# Pi1541_HAT.net
KiCad netlist of a schematic drawn in EAGLE
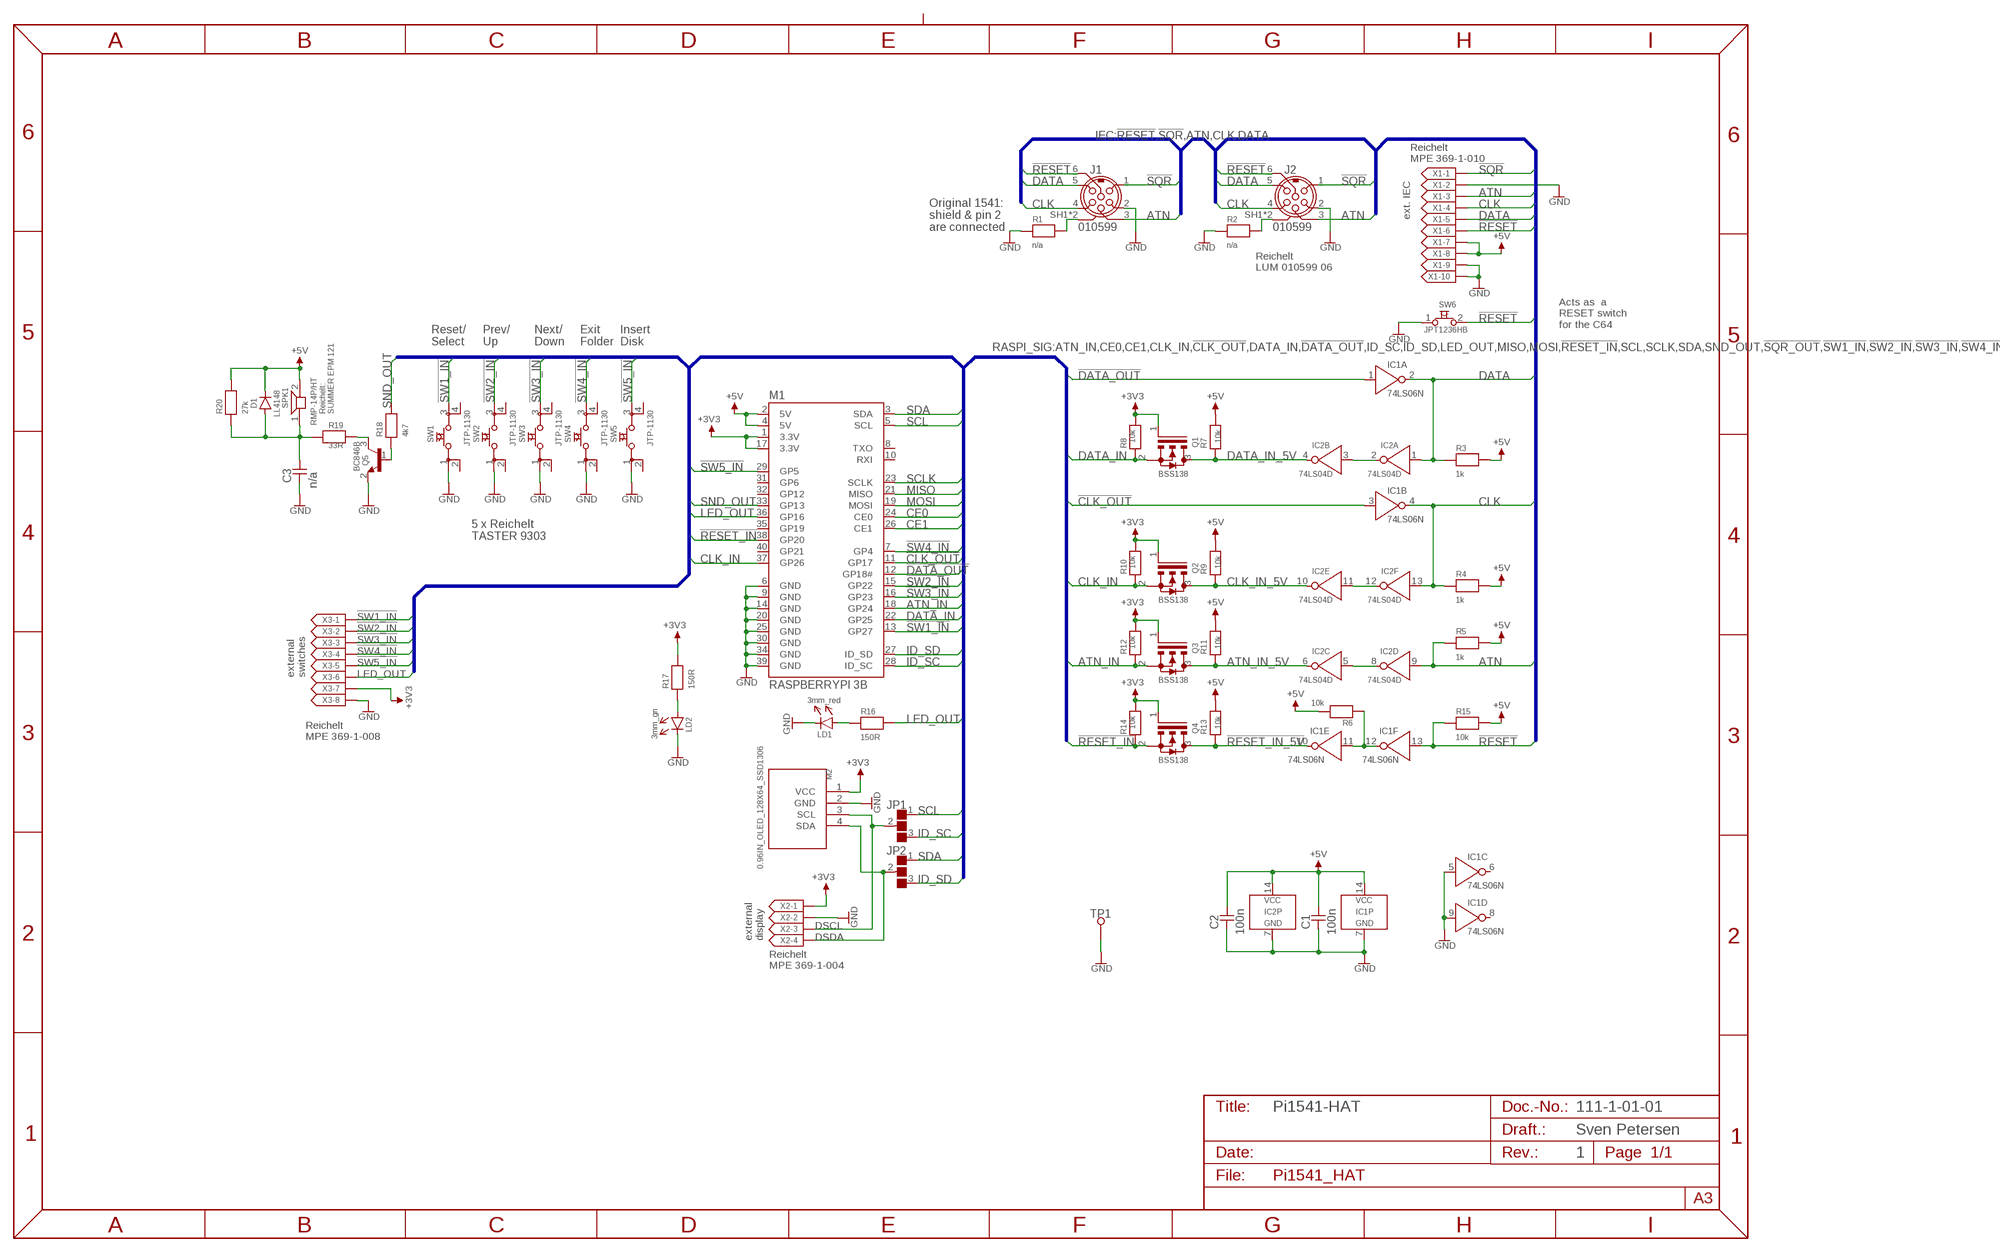
[diagram p0: schematic, sheet 1]

(export (version "E")
  (design (tool "Eeschema 10.0.6"))
  (components
    (comp (ref "C1")
      (value "100n")
      (footprint "eagle-import:0805")
      (libsource (lib "eagle-import") (part "C-0805"))
    )
    (comp (ref "C2")
      (value "100n")
      (footprint "eagle-import:0805")
      (libsource (lib "eagle-import") (part "C-0805"))
    )
    (comp (ref "C3")
      (value "n/a")
      (footprint "eagle-import:0805")
      (libsource (lib "eagle-import") (part "C-0805"))
    )
    (comp (ref "D1")
      (value "LL4148")
      (footprint "eagle-import:SOD80C")
      (libsource (lib "eagle-import") (part "LL4148"))
    )
    (comp (ref "IC1")
      (value "74LS06N")
      (footprint "eagle-import:DIL-14")
      (libsource (lib "eagle-import") (part "7406N"))
    )
    (comp (ref "IC2")
      (value "74LS04D")
      (footprint "eagle-import:SO-14")
      (libsource (lib "eagle-import") (part "7404HC"))
    )
    (comp (ref "J1")
      (value "010599")
      (footprint "eagle-import:010599")
      (libsource (lib "eagle-import") (part "010599"))
    )
    (comp (ref "J2")
      (value "010599")
      (footprint "eagle-import:010599")
      (libsource (lib "eagle-import") (part "010599"))
    )
    (comp (ref "JP1")
      (value "JMP_0603")
      (footprint "eagle-import:CP3P")
      (libsource (lib "eagle-import") (part "JMP_0603"))
    )
    (comp (ref "JP2")
      (value "JMP_0603")
      (footprint "eagle-import:CP3P")
      (libsource (lib "eagle-import") (part "JMP_0603"))
    )
    (comp (ref "LD1")
      (value "3mm_red")
      (footprint "eagle-import:3MM")
      (libsource (lib "eagle-import") (part "3MM"))
    )
    (comp (ref "LD2")
      (value "3mm_gn")
      (footprint "eagle-import:3MM")
      (libsource (lib "eagle-import") (part "3MM"))
    )
    (comp (ref "M1")
      (value "RASPBERRYPI 3B")
      (footprint "eagle-import:PI_HAT_40P")
      (libsource (lib "eagle-import") (part "RASPBERRYPI-40-PIN-GPIO"))
    )
    (comp (ref "M2")
      (value "0.96IN_OLED_128X64_SSD1306")
      (footprint "eagle-import:OLED_0.96_SSD1306")
      (libsource (lib "eagle-import") (part "0.96IN_OLED_128X64_SSD1306"))
    )
    (comp (ref "Q1")
      (value "BSS138")
      (footprint "eagle-import:SOT23")
      (libsource (lib "eagle-import") (part "BSS138"))
    )
    (comp (ref "Q2")
      (value "BSS138")
      (footprint "eagle-import:SOT23")
      (libsource (lib "eagle-import") (part "BSS138"))
    )
    (comp (ref "Q3")
      (value "BSS138")
      (footprint "eagle-import:SOT23")
      (libsource (lib "eagle-import") (part "BSS138"))
    )
    (comp (ref "Q4")
      (value "BSS138")
      (footprint "eagle-import:SOT23")
      (libsource (lib "eagle-import") (part "BSS138"))
    )
    (comp (ref "Q5")
      (value "BC846B")
      (footprint "eagle-import:SOT23")
      (libsource (lib "eagle-import") (part "BC846"))
    )
    (comp (ref "R1")
      (value "n/a")
      (footprint "eagle-import:0805")
      (libsource (lib "eagle-import") (part "R-0805"))
    )
    (comp (ref "R2")
      (value "n/a")
      (footprint "eagle-import:0805")
      (libsource (lib "eagle-import") (part "R-0805"))
    )
    (comp (ref "R3")
      (value "1k")
      (footprint "eagle-import:0805")
      (libsource (lib "eagle-import") (part "R-0805"))
    )
    (comp (ref "R4")
      (value "1k")
      (footprint "eagle-import:0805")
      (libsource (lib "eagle-import") (part "R-0805"))
    )
    (comp (ref "R5")
      (value "1k")
      (footprint "eagle-import:0805")
      (libsource (lib "eagle-import") (part "R-0805"))
    )
    (comp (ref "R6")
      (value "10k")
      (footprint "eagle-import:0805")
      (libsource (lib "eagle-import") (part "R-0805"))
    )
    (comp (ref "R7")
      (value "10k")
      (footprint "eagle-import:0805")
      (libsource (lib "eagle-import") (part "R-0805"))
    )
    (comp (ref "R8")
      (value "10k")
      (footprint "eagle-import:0805")
      (libsource (lib "eagle-import") (part "R-0805"))
    )
    (comp (ref "R9")
      (value "10k")
      (footprint "eagle-import:0805")
      (libsource (lib "eagle-import") (part "R-0805"))
    )
    (comp (ref "R10")
      (value "10k")
      (footprint "eagle-import:0805")
      (libsource (lib "eagle-import") (part "R-0805"))
    )
    (comp (ref "R11")
      (value "10k")
      (footprint "eagle-import:0805")
      (libsource (lib "eagle-import") (part "R-0805"))
    )
    (comp (ref "R12")
      (value "10k")
      (footprint "eagle-import:0805")
      (libsource (lib "eagle-import") (part "R-0805"))
    )
    (comp (ref "R13")
      (value "10k")
      (footprint "eagle-import:0805")
      (libsource (lib "eagle-import") (part "R-0805"))
    )
    (comp (ref "R14")
      (value "10k")
      (footprint "eagle-import:0805")
      (libsource (lib "eagle-import") (part "R-0805"))
    )
    (comp (ref "R15")
      (value "10k")
      (footprint "eagle-import:0805")
      (libsource (lib "eagle-import") (part "R-0805"))
    )
    (comp (ref "R16")
      (value "150R")
      (footprint "eagle-import:0805")
      (libsource (lib "eagle-import") (part "R-0805"))
    )
    (comp (ref "R17")
      (value "150R")
      (footprint "eagle-import:0805")
      (libsource (lib "eagle-import") (part "R-0805"))
    )
    (comp (ref "R18")
      (value "4k7")
      (footprint "eagle-import:0805")
      (libsource (lib "eagle-import") (part "R-0805"))
    )
    (comp (ref "R19")
      (value "33R")
      (footprint "eagle-import:0805")
      (libsource (lib "eagle-import") (part "R-0805"))
    )
    (comp (ref "R20")
      (value "27k")
      (footprint "eagle-import:0805")
      (libsource (lib "eagle-import") (part "R-0805"))
    )
    (comp (ref "SPK1")
      (value "RMP-14P/HT")
      (footprint "eagle-import:RMP-14P_HT")
      (libsource (lib "eagle-import") (part "RMP-14P/HT"))
    )
    (comp (ref "SW1")
      (value "JTP-1130")
      (footprint "eagle-import:JTP-1130")
      (libsource (lib "eagle-import") (part "JTP-1130"))
    )
    (comp (ref "SW2")
      (value "JTP-1130")
      (footprint "eagle-import:JTP-1130")
      (libsource (lib "eagle-import") (part "JTP-1130"))
    )
    (comp (ref "SW3")
      (value "JTP-1130")
      (footprint "eagle-import:JTP-1130")
      (libsource (lib "eagle-import") (part "JTP-1130"))
    )
    (comp (ref "SW4")
      (value "JTP-1130")
      (footprint "eagle-import:JTP-1130")
      (libsource (lib "eagle-import") (part "JTP-1130"))
    )
    (comp (ref "SW5")
      (value "JTP-1130")
      (footprint "eagle-import:JTP-1130")
      (libsource (lib "eagle-import") (part "JTP-1130"))
    )
    (comp (ref "SW6")
      (value "JPT1236HB")
      (footprint "eagle-import:JTP_1236HB")
      (libsource (lib "eagle-import") (part "JPT1236HB"))
    )
    (comp (ref "TP1")
      (value "L1,2_R")
      (footprint "eagle-import:1,2MM_R")
      (libsource (lib "eagle-import") (part "L1,2_R"))
    )
    (comp (ref "X1")
      (value "369-1-010")
      (footprint "eagle-import:MICMA10B")
      (libsource (lib "eagle-import") (part "MICMA10B-THT"))
    )
    (comp (ref "X2")
      (value "369-1-004")
      (footprint "eagle-import:MICMA04B")
      (libsource (lib "eagle-import") (part "MICMA04B-THR"))
    )
    (comp (ref "X3")
      (value "369-1-008")
      (footprint "eagle-import:MICMA08B")
      (libsource (lib "eagle-import") (part "MICMA08B"))
    )
  )
  (nets
    (net (code "4") (name "+3V3") (class "Default")
      (node (ref "M1") (pin "1") (pinfunction "3.3V_1") (pintype "power_in"))
      (node (ref "M1") (pin "17") (pinfunction "3.3V_17") (pintype "power_in"))
      (node (ref "M2") (pin "1") (pinfunction "VCC_1") (pintype "power_in"))
      (node (ref "Q1") (pin "1") (pinfunction "G_1") (pintype "bidirectional"))
      (node (ref "Q2") (pin "1") (pinfunction "G_1") (pintype "bidirectional"))
      (node (ref "Q3") (pin "1") (pinfunction "G_1") (pintype "bidirectional"))
      (node (ref "Q4") (pin "1") (pinfunction "G_1") (pintype "bidirectional"))
      (node (ref "R10") (pin "2") (pinfunction "2_2") (pintype "passive"))
      (node (ref "R12") (pin "2") (pinfunction "2_2") (pintype "passive"))
      (node (ref "R14") (pin "2") (pinfunction "2_2") (pintype "passive"))
      (node (ref "R17") (pin "2") (pinfunction "2_2") (pintype "passive"))
      (node (ref "R8") (pin "2") (pinfunction "2_2") (pintype "passive"))
      (node (ref "X2") (pin "1") (pinfunction "1_1") (pintype "bidirectional"))
      (node (ref "X3") (pin "7") (pinfunction "1_7") (pintype "bidirectional"))
    )
    (net (code "5") (name "+5V") (class "Default")
      (node (ref "C1") (pin "2") (pinfunction "2_2") (pintype "passive"))
      (node (ref "C2") (pin "2") (pinfunction "2_2") (pintype "passive"))
      (node (ref "D1") (pin "K") (pinfunction "K_K") (pintype "passive"))
      (node (ref "IC1") (pin "14") (pinfunction "VCC_14") (pintype "bidirectional"))
      (node (ref "IC2") (pin "14") (pinfunction "VCC_14") (pintype "bidirectional"))
      (node (ref "M1") (pin "2") (pinfunction "5V_2") (pintype "power_in"))
      (node (ref "M1") (pin "4") (pinfunction "5V_4") (pintype "power_in"))
      (node (ref "R11") (pin "2") (pinfunction "2_2") (pintype "passive"))
      (node (ref "R13") (pin "2") (pinfunction "2_2") (pintype "passive"))
      (node (ref "R15") (pin "2") (pinfunction "2_2") (pintype "passive"))
      (node (ref "R20") (pin "2") (pinfunction "2_2") (pintype "passive"))
      (node (ref "R3") (pin "2") (pinfunction "2_2") (pintype "passive"))
      (node (ref "R4") (pin "2") (pinfunction "2_2") (pintype "passive"))
      (node (ref "R5") (pin "2") (pinfunction "2_2") (pintype "passive"))
      (node (ref "R6") (pin "2") (pinfunction "2_2") (pintype "passive"))
      (node (ref "R7") (pin "2") (pinfunction "2_2") (pintype "passive"))
      (node (ref "R9") (pin "2") (pinfunction "2_2") (pintype "passive"))
      (node (ref "SPK1") (pin "2") (pinfunction "2_2") (pintype "bidirectional"))
      (node (ref "X1") (pin "7") (pinfunction "1_7") (pintype "bidirectional"))
      (node (ref "X1") (pin "8") (pinfunction "1_8") (pintype "bidirectional"))
    )
    (net (code "6") (name "/ATN") (class "Default")
      (node (ref "IC2") (pin "9") (pinfunction "I_9") (pintype "input"))
      (node (ref "J1") (pin "3") (pinfunction "3_3") (pintype "bidirectional"))
      (node (ref "J2") (pin "3") (pinfunction "3_3") (pintype "bidirectional"))
      (node (ref "R5") (pin "1") (pinfunction "1_1") (pintype "passive"))
      (node (ref "X1") (pin "3") (pinfunction "1_3") (pintype "bidirectional"))
    )
    (net (code "7") (name "/ATN_IN") (class "Default")
      (node (ref "M1") (pin "18") (pinfunction "GP24_18") (pintype "bidirectional"))
      (node (ref "Q3") (pin "2") (pinfunction "S_2") (pintype "bidirectional"))
      (node (ref "R12") (pin "1") (pinfunction "1_1") (pintype "passive"))
    )
    (net (code "8") (name "/ATN_IN_5V") (class "Default")
      (node (ref "IC2") (pin "6") (pinfunction "O_6") (pintype "output"))
      (node (ref "Q3") (pin "3") (pinfunction "D_3") (pintype "bidirectional"))
      (node (ref "R11") (pin "1") (pinfunction "1_1") (pintype "passive"))
    )
    (net (code "9") (name "/CE0") (class "Default")
      (node (ref "M1") (pin "24") (pinfunction "CE0_24") (pintype "output"))
    )
    (net (code "10") (name "/CE1") (class "Default")
      (node (ref "M1") (pin "26") (pinfunction "CE1_26") (pintype "output"))
    )
    (net (code "11") (name "/CLK") (class "Default")
      (node (ref "IC1") (pin "4") (pinfunction "O_4") (pintype "open_collector"))
      (node (ref "IC2") (pin "13") (pinfunction "I_13") (pintype "input"))
      (node (ref "J1") (pin "4") (pinfunction "4_4") (pintype "bidirectional"))
      (node (ref "J2") (pin "4") (pinfunction "4_4") (pintype "bidirectional"))
      (node (ref "R4") (pin "1") (pinfunction "1_1") (pintype "passive"))
      (node (ref "X1") (pin "4") (pinfunction "1_4") (pintype "bidirectional"))
    )
    (net (code "12") (name "/CLK_IN") (class "Default")
      (node (ref "M1") (pin "37") (pinfunction "GP26_37") (pintype "bidirectional"))
      (node (ref "Q2") (pin "2") (pinfunction "S_2") (pintype "bidirectional"))
      (node (ref "R10") (pin "1") (pinfunction "1_1") (pintype "passive"))
    )
    (net (code "13") (name "/CLK_IN_5V") (class "Default")
      (node (ref "IC2") (pin "10") (pinfunction "O_10") (pintype "output"))
      (node (ref "Q2") (pin "3") (pinfunction "D_3") (pintype "bidirectional"))
      (node (ref "R9") (pin "1") (pinfunction "1_1") (pintype "passive"))
    )
    (net (code "14") (name "/DATA") (class "Default")
      (node (ref "IC1") (pin "2") (pinfunction "O_2") (pintype "open_collector"))
      (node (ref "IC2") (pin "1") (pinfunction "I_1") (pintype "input"))
      (node (ref "J1") (pin "5") (pinfunction "5_5") (pintype "bidirectional"))
      (node (ref "J2") (pin "5") (pinfunction "5_5") (pintype "bidirectional"))
      (node (ref "R3") (pin "1") (pinfunction "1_1") (pintype "passive"))
      (node (ref "X1") (pin "5") (pinfunction "1_5") (pintype "bidirectional"))
    )
    (net (code "15") (name "/DATA_IN") (class "Default")
      (node (ref "M1") (pin "22") (pinfunction "GP25_22") (pintype "bidirectional"))
      (node (ref "Q1") (pin "2") (pinfunction "S_2") (pintype "bidirectional"))
      (node (ref "R8") (pin "1") (pinfunction "1_1") (pintype "passive"))
    )
    (net (code "16") (name "/DATA_IN_5V") (class "Default")
      (node (ref "IC2") (pin "4") (pinfunction "O_4") (pintype "output"))
      (node (ref "Q1") (pin "3") (pinfunction "D_3") (pintype "bidirectional"))
      (node (ref "R7") (pin "1") (pinfunction "1_1") (pintype "passive"))
    )
    (net (code "17") (name "/DSCL") (class "Default")
      (node (ref "JP1") (pin "2") (pinfunction "2_2") (pintype "bidirectional"))
      (node (ref "M2") (pin "3") (pinfunction "SCL_3") (pintype "input"))
      (node (ref "X2") (pin "3") (pinfunction "1_3") (pintype "bidirectional"))
    )
    (net (code "18") (name "/DSDA") (class "Default")
      (node (ref "JP2") (pin "2") (pinfunction "2_2") (pintype "bidirectional"))
      (node (ref "M2") (pin "4") (pinfunction "SDA_4") (pintype "bidirectional"))
      (node (ref "X2") (pin "4") (pinfunction "1_4") (pintype "bidirectional"))
    )
    (net (code "19") (name "/ID_SC") (class "Default")
      (node (ref "JP1") (pin "3") (pinfunction "3_3") (pintype "bidirectional"))
      (node (ref "M1") (pin "28") (pinfunction "ID_SC_28") (pintype "bidirectional"))
    )
    (net (code "20") (name "/ID_SD") (class "Default")
      (node (ref "JP2") (pin "3") (pinfunction "3_3") (pintype "bidirectional"))
      (node (ref "M1") (pin "27") (pinfunction "ID_SD_27") (pintype "bidirectional"))
    )
    (net (code "21") (name "/LED_OUT") (class "Default")
      (node (ref "M1") (pin "36") (pinfunction "GP16_36") (pintype "bidirectional"))
      (node (ref "R16") (pin "2") (pinfunction "2_2") (pintype "passive"))
      (node (ref "X3") (pin "6") (pinfunction "1_6") (pintype "bidirectional"))
    )
    (net (code "22") (name "/MISO") (class "Default")
      (node (ref "M1") (pin "21") (pinfunction "MISO_21") (pintype "input"))
    )
    (net (code "23") (name "/MOSI") (class "Default")
      (node (ref "M1") (pin "19") (pinfunction "MOSI_19") (pintype "output"))
    )
    (net (code "24") (name "/SCL") (class "Default")
      (node (ref "JP1") (pin "1") (pinfunction "1_1") (pintype "bidirectional"))
      (node (ref "M1") (pin "5") (pinfunction "SCL_5") (pintype "bidirectional"))
    )
    (net (code "25") (name "/SCLK") (class "Default")
      (node (ref "M1") (pin "23") (pinfunction "SCLK_23") (pintype "output"))
    )
    (net (code "26") (name "/SDA") (class "Default")
      (node (ref "JP2") (pin "1") (pinfunction "1_1") (pintype "bidirectional"))
      (node (ref "M1") (pin "3") (pinfunction "SDA_3") (pintype "bidirectional"))
    )
    (net (code "27") (name "/SND_OUT") (class "Default")
      (node (ref "M1") (pin "33") (pinfunction "GP13_33") (pintype "bidirectional"))
      (node (ref "R18") (pin "2") (pinfunction "2_2") (pintype "passive"))
    )
    (net (code "30") (name "/~{CLK_OUT}") (class "Default")
      (node (ref "IC1") (pin "3") (pinfunction "I_3") (pintype "input"))
      (node (ref "M1") (pin "11") (pinfunction "GP17_11") (pintype "bidirectional"))
    )
    (net (code "31") (name "/~{DATA_OUT}") (class "Default")
      (node (ref "IC1") (pin "1") (pinfunction "I_1") (pintype "input"))
      (node (ref "M1") (pin "12") (pinfunction "GP18#_12") (pintype "bidirectional"))
    )
    (net (code "32") (name "/~{RESET_IN_5V}") (class "Default")
      (node (ref "IC1") (pin "10") (pinfunction "O_10") (pintype "open_collector"))
      (node (ref "Q4") (pin "3") (pinfunction "D_3") (pintype "bidirectional"))
      (node (ref "R13") (pin "1") (pinfunction "1_1") (pintype "passive"))
    )
    (net (code "33") (name "/~{RESET_IN}") (class "Default")
      (node (ref "M1") (pin "38") (pinfunction "GP20_38") (pintype "bidirectional"))
      (node (ref "Q4") (pin "2") (pinfunction "S_2") (pintype "bidirectional"))
      (node (ref "R14") (pin "1") (pinfunction "1_1") (pintype "passive"))
    )
    (net (code "34") (name "/~{RESET}") (class "Default")
      (node (ref "IC1") (pin "13") (pinfunction "I_13") (pintype "input"))
      (node (ref "J1") (pin "6") (pinfunction "6_6") (pintype "bidirectional"))
      (node (ref "J2") (pin "6") (pinfunction "6_6") (pintype "bidirectional"))
      (node (ref "R15") (pin "1") (pinfunction "1_1") (pintype "passive"))
      (node (ref "SW6") (pin "2") (pinfunction "2_2") (pintype "passive"))
      (node (ref "X1") (pin "6") (pinfunction "1_6") (pintype "bidirectional"))
    )
    (net (code "35") (name "/~{SQR}") (class "Default")
      (node (ref "J1") (pin "1") (pinfunction "1_1") (pintype "bidirectional"))
      (node (ref "J2") (pin "1") (pinfunction "1_1") (pintype "bidirectional"))
      (node (ref "X1") (pin "1") (pinfunction "1_1") (pintype "bidirectional"))
    )
    (net (code "36") (name "/~{SW1_IN}") (class "Default")
      (node (ref "M1") (pin "13") (pinfunction "GP27_13") (pintype "bidirectional"))
      (node (ref "SW1") (pin "3") (pinfunction "3_3") (pintype "passive"))
      (node (ref "X3") (pin "1") (pinfunction "1_1") (pintype "bidirectional"))
    )
    (net (code "37") (name "/~{SW2_IN}") (class "Default")
      (node (ref "M1") (pin "15") (pinfunction "GP22_15") (pintype "bidirectional"))
      (node (ref "SW2") (pin "3") (pinfunction "3_3") (pintype "passive"))
      (node (ref "X3") (pin "2") (pinfunction "1_2") (pintype "bidirectional"))
    )
    (net (code "38") (name "/~{SW3_IN}") (class "Default")
      (node (ref "M1") (pin "16") (pinfunction "GP23_16") (pintype "bidirectional"))
      (node (ref "SW3") (pin "3") (pinfunction "3_3") (pintype "passive"))
      (node (ref "X3") (pin "3") (pinfunction "1_3") (pintype "bidirectional"))
    )
    (net (code "39") (name "/~{SW4_IN}") (class "Default")
      (node (ref "M1") (pin "7") (pinfunction "GP4_7") (pintype "bidirectional"))
      (node (ref "SW4") (pin "3") (pinfunction "3_3") (pintype "passive"))
      (node (ref "X3") (pin "4") (pinfunction "1_4") (pintype "bidirectional"))
    )
    (net (code "40") (name "/~{SW5_IN}") (class "Default")
      (node (ref "M1") (pin "29") (pinfunction "GP5_29") (pintype "bidirectional"))
      (node (ref "SW5") (pin "3") (pinfunction "3_3") (pintype "passive"))
      (node (ref "X3") (pin "5") (pinfunction "1_5") (pintype "bidirectional"))
    )
    (net (code "41") (name "GND") (class "Default")
      (node (ref "C1") (pin "1") (pinfunction "1_1") (pintype "passive"))
      (node (ref "C2") (pin "1") (pinfunction "1_1") (pintype "passive"))
      (node (ref "C3") (pin "1") (pinfunction "1_1") (pintype "passive"))
      (node (ref "IC1") (pin "5") (pinfunction "I_5") (pintype "input"))
      (node (ref "IC1") (pin "7") (pinfunction "GND_7") (pintype "bidirectional"))
      (node (ref "IC1") (pin "9") (pinfunction "I_9") (pintype "input"))
      (node (ref "IC2") (pin "7") (pinfunction "GND_7") (pintype "bidirectional"))
      (node (ref "J1") (pin "2") (pinfunction "2_2") (pintype "bidirectional"))
      (node (ref "J2") (pin "2") (pinfunction "2_2") (pintype "bidirectional"))
      (node (ref "LD1") (pin "K") (pinfunction "K_K") (pintype "bidirectional"))
      (node (ref "LD2") (pin "K") (pinfunction "K_K") (pintype "bidirectional"))
      (node (ref "M1") (pin "14") (pinfunction "GND_14") (pintype "power_in"))
      (node (ref "M1") (pin "20") (pinfunction "GND_20") (pintype "power_in"))
      (node (ref "M1") (pin "25") (pinfunction "GND_25") (pintype "power_in"))
      (node (ref "M1") (pin "30") (pinfunction "GND_30") (pintype "power_in"))
      (node (ref "M1") (pin "34") (pinfunction "GND_34") (pintype "power_in"))
      (node (ref "M1") (pin "39") (pinfunction "GND_39") (pintype "power_in"))
      (node (ref "M1") (pin "6") (pinfunction "GND_6") (pintype "power_in"))
      (node (ref "M1") (pin "9") (pinfunction "GND_9") (pintype "power_in"))
      (node (ref "M2") (pin "2") (pinfunction "GND_2") (pintype "power_in"))
      (node (ref "Q5") (pin "2") (pinfunction "E_2") (pintype "passive"))
      (node (ref "R1") (pin "1") (pinfunction "1_1") (pintype "passive"))
      (node (ref "R2") (pin "1") (pinfunction "1_1") (pintype "passive"))
      (node (ref "SW1") (pin "1") (pinfunction "1_1") (pintype "passive"))
      (node (ref "SW2") (pin "1") (pinfunction "1_1") (pintype "passive"))
      (node (ref "SW3") (pin "1") (pinfunction "1_1") (pintype "passive"))
      (node (ref "SW4") (pin "1") (pinfunction "1_1") (pintype "passive"))
      (node (ref "SW5") (pin "1") (pinfunction "1_1") (pintype "passive"))
      (node (ref "SW6") (pin "1") (pinfunction "1_1") (pintype "passive"))
      (node (ref "TP1") (pin "1") (pinfunction "1_1") (pintype "passive"))
      (node (ref "X1") (pin "10") (pinfunction "1_10") (pintype "bidirectional"))
      (node (ref "X1") (pin "2") (pinfunction "1_2") (pintype "bidirectional"))
      (node (ref "X1") (pin "9") (pinfunction "1_9") (pintype "bidirectional"))
      (node (ref "X2") (pin "2") (pinfunction "1_2") (pintype "bidirectional"))
      (node (ref "X3") (pin "8") (pinfunction "1_8") (pintype "bidirectional"))
    )
    (net (code "42") (name "Net-(C3-Pad2)") (class "Default")
      (node (ref "C3") (pin "2") (pinfunction "2_2") (pintype "passive"))
      (node (ref "D1") (pin "A") (pinfunction "A_A") (pintype "passive"))
      (node (ref "R19") (pin "1") (pinfunction "1_1") (pintype "passive"))
      (node (ref "R20") (pin "1") (pinfunction "1_1") (pintype "passive"))
      (node (ref "SPK1") (pin "1") (pinfunction "1_1") (pintype "bidirectional"))
    )
    (net (code "43") (name "Net-(IC1E-I)") (class "Default")
      (node (ref "IC1") (pin "11") (pinfunction "I_11") (pintype "input"))
      (node (ref "IC1") (pin "12") (pinfunction "O_12") (pintype "open_collector"))
      (node (ref "R6") (pin "1") (pinfunction "1_1") (pintype "passive"))
    )
    (net (code "44") (name "Net-(IC2A-O)") (class "Default")
      (node (ref "IC2") (pin "2") (pinfunction "O_2") (pintype "output"))
      (node (ref "IC2") (pin "3") (pinfunction "I_3") (pintype "input"))
    )
    (net (code "45") (name "Net-(IC2C-I)") (class "Default")
      (node (ref "IC2") (pin "5") (pinfunction "I_5") (pintype "input"))
      (node (ref "IC2") (pin "8") (pinfunction "O_8") (pintype "output"))
    )
    (net (code "46") (name "Net-(IC2E-I)") (class "Default")
      (node (ref "IC2") (pin "11") (pinfunction "I_11") (pintype "input"))
      (node (ref "IC2") (pin "12") (pinfunction "O_12") (pintype "output"))
    )
    (net (code "47") (name "Net-(J1-SH-PadSH1)") (class "Default")
      (node (ref "J1") (pin "SH1") (pinfunction "SH_SH1") (pintype "bidirectional"))
      (node (ref "J1") (pin "SH2") (pinfunction "SH_SH2") (pintype "bidirectional"))
      (node (ref "R1") (pin "2") (pinfunction "2_2") (pintype "passive"))
    )
    (net (code "48") (name "Net-(J2-SH-PadSH1)") (class "Default")
      (node (ref "J2") (pin "SH1") (pinfunction "SH_SH1") (pintype "bidirectional"))
      (node (ref "J2") (pin "SH2") (pinfunction "SH_SH2") (pintype "bidirectional"))
      (node (ref "R2") (pin "2") (pinfunction "2_2") (pintype "passive"))
    )
    (net (code "49") (name "Net-(LD1-PadA)") (class "Default")
      (node (ref "LD1") (pin "A") (pinfunction "A_A") (pintype "bidirectional"))
      (node (ref "R16") (pin "1") (pinfunction "1_1") (pintype "passive"))
    )
    (net (code "50") (name "Net-(LD2-PadA)") (class "Default")
      (node (ref "LD2") (pin "A") (pinfunction "A_A") (pintype "bidirectional"))
      (node (ref "R17") (pin "1") (pinfunction "1_1") (pintype "passive"))
    )
    (net (code "51") (name "Net-(Q5-B)") (class "Default")
      (node (ref "Q5") (pin "1") (pinfunction "B_1") (pintype "passive"))
      (node (ref "R18") (pin "1") (pinfunction "1_1") (pintype "passive"))
    )
    (net (code "52") (name "Net-(Q5-C)") (class "Default")
      (node (ref "Q5") (pin "3") (pinfunction "C_3") (pintype "passive"))
      (node (ref "R19") (pin "2") (pinfunction "2_2") (pintype "passive"))
    )
    (net (code "53") (name "unconnected-(IC1C-O-Pad6)") (class "Default")
      (node (ref "IC1") (pin "6") (pinfunction "O_6") (pintype "open_collector"))
    )
    (net (code "54") (name "unconnected-(IC1D-O-Pad8)") (class "Default")
      (node (ref "IC1") (pin "8") (pinfunction "O_8") (pintype "open_collector"))
    )
    (net (code "55") (name "unconnected-(M1-GP6-Pad31)") (class "Default")
      (node (ref "M1") (pin "31") (pinfunction "GP6_31") (pintype "bidirectional"))
    )
    (net (code "56") (name "unconnected-(M1-GP12-Pad32)") (class "Default")
      (node (ref "M1") (pin "32") (pinfunction "GP12_32") (pintype "bidirectional"))
    )
    (net (code "57") (name "unconnected-(M1-GP19-Pad35)") (class "Default")
      (node (ref "M1") (pin "35") (pinfunction "GP19_35") (pintype "bidirectional"))
    )
    (net (code "58") (name "unconnected-(M1-GP21-Pad40)") (class "Default")
      (node (ref "M1") (pin "40") (pinfunction "GP21_40") (pintype "bidirectional"))
    )
    (net (code "59") (name "unconnected-(M1-RXI-Pad10)") (class "Default")
      (node (ref "M1") (pin "10") (pinfunction "RXI_10") (pintype "input"))
    )
    (net (code "60") (name "unconnected-(M1-TXO-Pad8)") (class "Default")
      (node (ref "M1") (pin "8") (pinfunction "TXO_8") (pintype "output"))
    )
    (net (code "61") (name "unconnected-(SW1-Pad2)") (class "Default")
      (node (ref "SW1") (pin "2") (pinfunction "2_2") (pintype "passive"))
    )
    (net (code "62") (name "unconnected-(SW1-Pad4)") (class "Default")
      (node (ref "SW1") (pin "4") (pinfunction "4_4") (pintype "passive"))
    )
    (net (code "63") (name "unconnected-(SW2-Pad2)") (class "Default")
      (node (ref "SW2") (pin "2") (pinfunction "2_2") (pintype "passive"))
    )
    (net (code "64") (name "unconnected-(SW2-Pad4)") (class "Default")
      (node (ref "SW2") (pin "4") (pinfunction "4_4") (pintype "passive"))
    )
    (net (code "65") (name "unconnected-(SW3-Pad2)") (class "Default")
      (node (ref "SW3") (pin "2") (pinfunction "2_2") (pintype "passive"))
    )
    (net (code "66") (name "unconnected-(SW3-Pad4)") (class "Default")
      (node (ref "SW3") (pin "4") (pinfunction "4_4") (pintype "passive"))
    )
    (net (code "67") (name "unconnected-(SW4-Pad2)") (class "Default")
      (node (ref "SW4") (pin "2") (pinfunction "2_2") (pintype "passive"))
    )
    (net (code "68") (name "unconnected-(SW4-Pad4)") (class "Default")
      (node (ref "SW4") (pin "4") (pinfunction "4_4") (pintype "passive"))
    )
    (net (code "69") (name "unconnected-(SW5-Pad2)") (class "Default")
      (node (ref "SW5") (pin "2") (pinfunction "2_2") (pintype "passive"))
    )
    (net (code "70") (name "unconnected-(SW5-Pad4)") (class "Default")
      (node (ref "SW5") (pin "4") (pinfunction "4_4") (pintype "passive"))
    )
  )
)
